# 1A19J2_1A20J17_B.net
KiCad netlist of a schematic drawn in Altium Designer
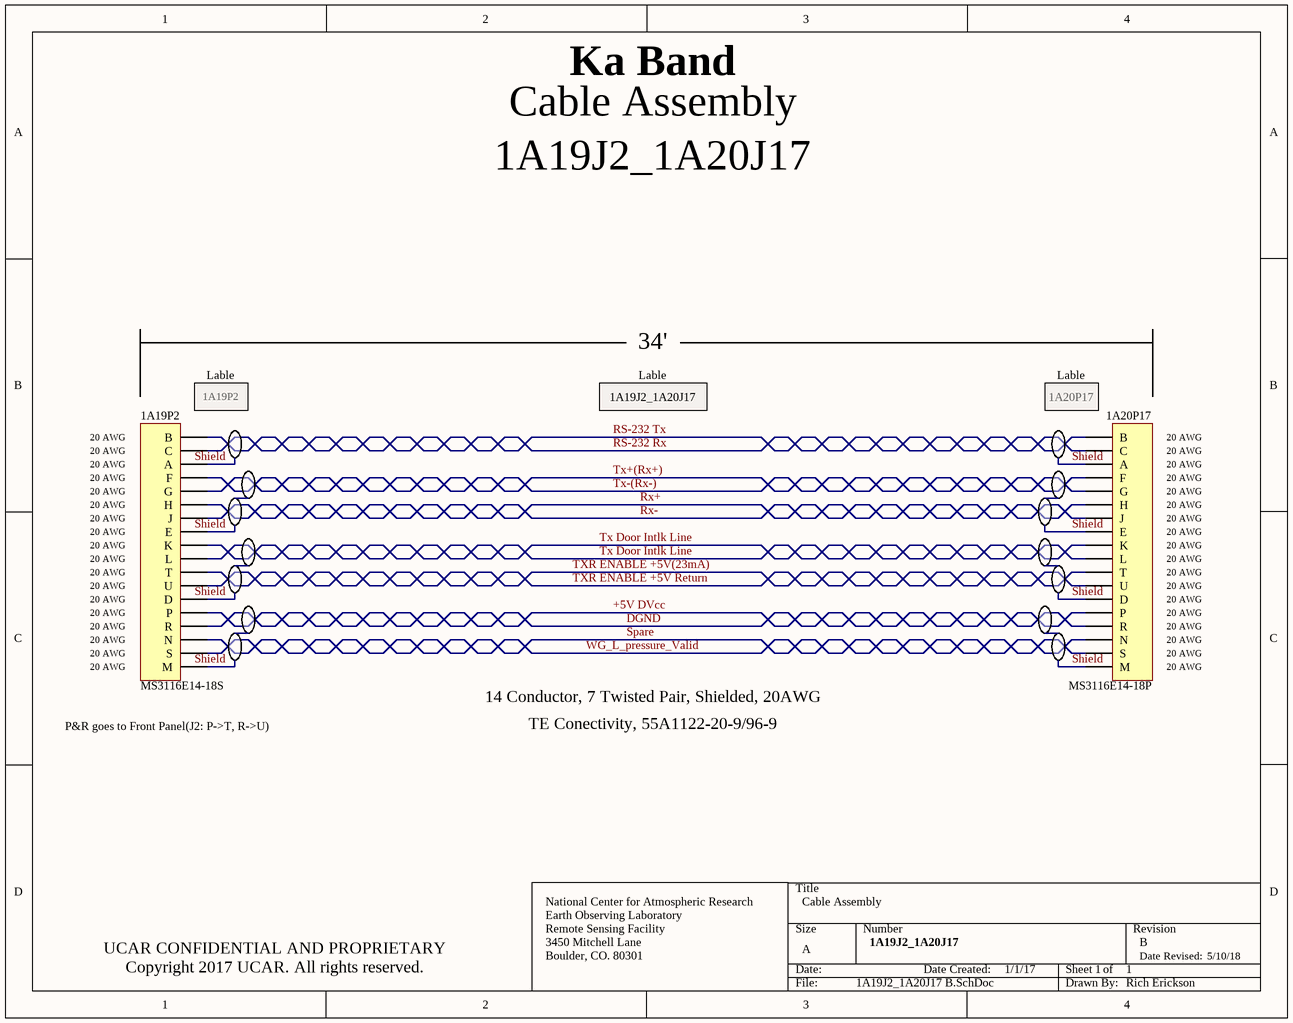
[diagram p0: 1A19J2_1A20J17 B.SchDoc]

(export (version "E")
  (design (tool "Eeschema 10.0.6"))
  (components
    (comp (ref "1A19P2")
      (value "MS3116E14-18S")
      (footprint "HDR1X18")
      (description "Header, 18-Pin")
      (fields (field (name "PUBLISHER") "Altium Limited"))
      (libsource (lib "Miscellaneous Connectors") (part "Header 18"))
    )
    (comp (ref "1A20P17")
      (value "MS3116E14-18P")
      (footprint "HDR1X18")
      (description "Header, 18-Pin")
      (fields (field (name "PUBLISHER") "Altium Limited"))
      (libsource (lib "") (part "Header 18_1"))
    )
  )
  (nets
    (net (code "1") (name "/+5V DVcc") (class "Default")
      (node (ref "1A19P2") (pin "14") (pinfunction "P_14") (pintype "passive"))
      (node (ref "1A20P17") (pin "14") (pinfunction "P_14") (pintype "passive"))
    )
    (net (code "2") (name "/DGND") (class "Default")
      (node (ref "1A19P2") (pin "15") (pinfunction "R_15") (pintype "passive"))
      (node (ref "1A20P17") (pin "15") (pinfunction "R_15") (pintype "passive"))
    )
    (net (code "3") (name "/RS-232 Rx") (class "Default")
      (node (ref "1A19P2") (pin "2") (pinfunction "C_2") (pintype "passive"))
      (node (ref "1A20P17") (pin "2") (pinfunction "C_2") (pintype "passive"))
    )
    (net (code "4") (name "/RS-232 Tx") (class "Default")
      (node (ref "1A19P2") (pin "1") (pinfunction "B_1") (pintype "passive"))
      (node (ref "1A20P17") (pin "1") (pinfunction "B_1") (pintype "passive"))
    )
    (net (code "5") (name "/Rx+") (class "Default")
      (node (ref "1A19P2") (pin "6") (pinfunction "H_6") (pintype "passive"))
      (node (ref "1A20P17") (pin "6") (pinfunction "H_6") (pintype "passive"))
    )
    (net (code "6") (name "/Rx-") (class "Default")
      (node (ref "1A19P2") (pin "7") (pinfunction "J_7") (pintype "passive"))
      (node (ref "1A20P17") (pin "7") (pinfunction "J_7") (pintype "passive"))
    )
    (net (code "7") (name "/Shield") (class "Default")
      (node (ref "1A20P17") (pin "13") (pinfunction "D_13") (pintype "passive"))
      (node (ref "1A20P17") (pin "18") (pinfunction "M_18") (pintype "passive"))
      (node (ref "1A20P17") (pin "3") (pinfunction "A_3") (pintype "passive"))
      (node (ref "1A20P17") (pin "8") (pinfunction "E_8") (pintype "passive"))
    )
    (net (code "8") (name "/Spare") (class "Default")
      (node (ref "1A19P2") (pin "16") (pinfunction "N_16") (pintype "passive"))
      (node (ref "1A20P17") (pin "16") (pinfunction "N_16") (pintype "passive"))
    )
    (net (code "9") (name "/TXR ENABLE +5V Return") (class "Default")
      (node (ref "1A19P2") (pin "12") (pinfunction "U_12") (pintype "passive"))
      (node (ref "1A20P17") (pin "12") (pinfunction "U_12") (pintype "passive"))
    )
    (net (code "10") (name "/TXR ENABLE +5V(23mA)") (class "Default")
      (node (ref "1A19P2") (pin "11") (pinfunction "T_11") (pintype "passive"))
      (node (ref "1A20P17") (pin "11") (pinfunction "T_11") (pintype "passive"))
    )
    (net (code "11") (name "/Tx Door Intlk Line") (class "Default")
      (node (ref "1A19P2") (pin "10") (pinfunction "L_10") (pintype "passive"))
      (node (ref "1A19P2") (pin "9") (pinfunction "K_9") (pintype "passive"))
      (node (ref "1A20P17") (pin "10") (pinfunction "L_10") (pintype "passive"))
      (node (ref "1A20P17") (pin "9") (pinfunction "K_9") (pintype "passive"))
    )
    (net (code "12") (name "/Tx+(Rx+)") (class "Default")
      (node (ref "1A19P2") (pin "4") (pinfunction "F_4") (pintype "passive"))
      (node (ref "1A20P17") (pin "4") (pinfunction "F_4") (pintype "passive"))
    )
    (net (code "13") (name "/Tx-(Rx-)") (class "Default")
      (node (ref "1A19P2") (pin "5") (pinfunction "G_5") (pintype "passive"))
      (node (ref "1A20P17") (pin "5") (pinfunction "G_5") (pintype "passive"))
    )
    (net (code "14") (name "/WG_L_pressure_Valid") (class "Default")
      (node (ref "1A19P2") (pin "17") (pinfunction "S_17") (pintype "passive"))
      (node (ref "1A20P17") (pin "17") (pinfunction "S_17") (pintype "passive"))
    )
    (net (code "15") (name "unconnected-(1A19P2-A-Pad3)") (class "Default")
      (node (ref "1A19P2") (pin "3") (pinfunction "A_3") (pintype "passive"))
    )
    (net (code "16") (name "unconnected-(1A19P2-D-Pad13)") (class "Default")
      (node (ref "1A19P2") (pin "13") (pinfunction "D_13") (pintype "passive"))
    )
    (net (code "17") (name "unconnected-(1A19P2-E-Pad8)") (class "Default")
      (node (ref "1A19P2") (pin "8") (pinfunction "E_8") (pintype "passive"))
    )
    (net (code "18") (name "unconnected-(1A19P2-M-Pad18)") (class "Default")
      (node (ref "1A19P2") (pin "18") (pinfunction "M_18") (pintype "passive"))
    )
  )
)
